# Microcontroller.net
KiCad netlist of a schematic drawn in Altium Designer
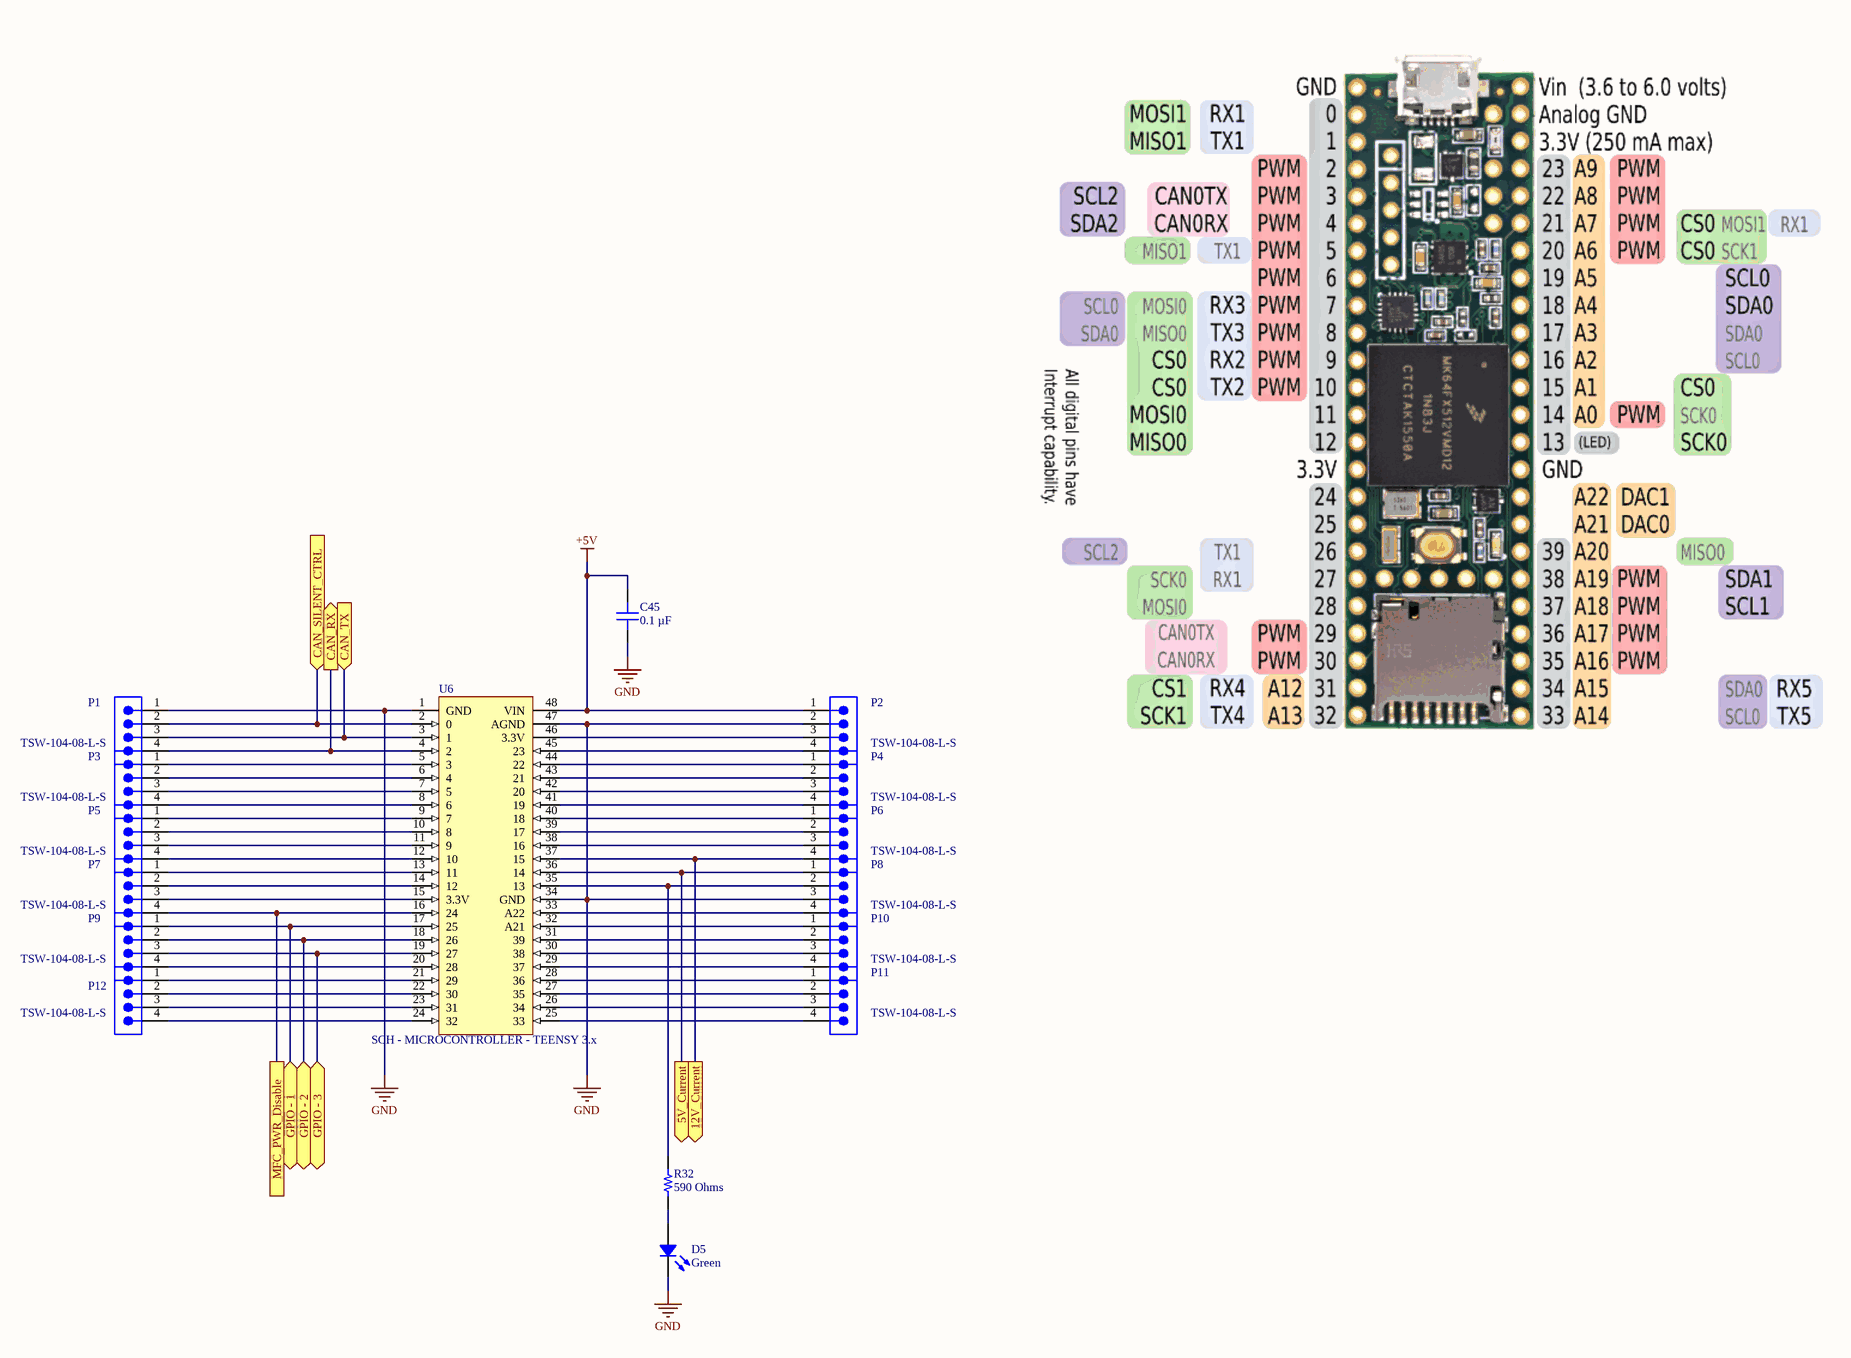
[diagram p0: Microcontroller.SchDoc]

(export (version "E")
  (design (tool "Eeschema 10.0.6"))
  (components
    (comp (ref "C45")
      (value "0.1 µF")
      (footprint "CAP 0603_1608")
      (description "CAP CER 0.1UF 50V X7R 0603")
      (fields
        (field (name "PART NUMBER") "CL10B104KB8NNWC")
        (field (name "MANUFACTURER") "Samsung Electro-Mechanics")
      )
      (libsource (lib "Celestial Altium Library - altium_library") (part "Capacitor"))
    )
    (comp (ref "D5")
      (value "Green")
      (footprint "LED 0603_1608 GREEN")
      (description "LED GREEN CLEAR CHIP SMD")
      (fields (field (name "PART NUMBER") "LTST-C193KGKT-5A") (field (name "MANUFACTURER") "Lite-On Inc."))
      (libsource (lib "Celestial Altium Library - altium_library") (part "LED"))
    )
    (comp (ref "P1")
      (value "TSW-104-08-L-S")
      (footprint "SMTC-TSW-104-08-X-S")
      (description "0.025\" SQ Post Header, Through-hole, Vertical, -55 to 125 degC, 2.54 mm Pitch, 4-Pin, Male, RoHS")
      (fields (field (name "MANUFACTURER") "Samtec"))
      (libsource (lib "Altium Content Vault") (part "SMTC-TSW-104-08-X-S"))
    )
    (comp (ref "P2")
      (value "TSW-104-08-L-S")
      (footprint "SMTC-TSW-104-08-X-S")
      (description "0.025\" SQ Post Header, Through-hole, Vertical, -55 to 125 degC, 2.54 mm Pitch, 4-Pin, Male, RoHS")
      (fields (field (name "MANUFACTURER") "Samtec"))
      (libsource (lib "Altium Content Vault") (part "SMTC-TSW-104-08-X-S"))
    )
    (comp (ref "P3")
      (value "TSW-104-08-L-S")
      (footprint "SMTC-TSW-104-08-X-S")
      (description "0.025\" SQ Post Header, Through-hole, Vertical, -55 to 125 degC, 2.54 mm Pitch, 4-Pin, Male, RoHS")
      (fields (field (name "MANUFACTURER") "Samtec"))
      (libsource (lib "Altium Content Vault") (part "SMTC-TSW-104-08-X-S"))
    )
    (comp (ref "P4")
      (value "TSW-104-08-L-S")
      (footprint "SMTC-TSW-104-08-X-S")
      (description "0.025\" SQ Post Header, Through-hole, Vertical, -55 to 125 degC, 2.54 mm Pitch, 4-Pin, Male, RoHS")
      (fields (field (name "MANUFACTURER") "Samtec"))
      (libsource (lib "Altium Content Vault") (part "SMTC-TSW-104-08-X-S"))
    )
    (comp (ref "P5")
      (value "TSW-104-08-L-S")
      (footprint "SMTC-TSW-104-08-X-S")
      (description "0.025\" SQ Post Header, Through-hole, Vertical, -55 to 125 degC, 2.54 mm Pitch, 4-Pin, Male, RoHS")
      (fields (field (name "MANUFACTURER") "Samtec"))
      (libsource (lib "Altium Content Vault") (part "SMTC-TSW-104-08-X-S"))
    )
    (comp (ref "P6")
      (value "TSW-104-08-L-S")
      (footprint "SMTC-TSW-104-08-X-S")
      (description "0.025\" SQ Post Header, Through-hole, Vertical, -55 to 125 degC, 2.54 mm Pitch, 4-Pin, Male, RoHS")
      (fields (field (name "MANUFACTURER") "Samtec"))
      (libsource (lib "Altium Content Vault") (part "SMTC-TSW-104-08-X-S"))
    )
    (comp (ref "P7")
      (value "TSW-104-08-L-S")
      (footprint "SMTC-TSW-104-08-X-S")
      (description "0.025\" SQ Post Header, Through-hole, Vertical, -55 to 125 degC, 2.54 mm Pitch, 4-Pin, Male, RoHS")
      (fields (field (name "MANUFACTURER") "Samtec"))
      (libsource (lib "Altium Content Vault") (part "SMTC-TSW-104-08-X-S"))
    )
    (comp (ref "P8")
      (value "TSW-104-08-L-S")
      (footprint "SMTC-TSW-104-08-X-S")
      (description "0.025\" SQ Post Header, Through-hole, Vertical, -55 to 125 degC, 2.54 mm Pitch, 4-Pin, Male, RoHS")
      (fields (field (name "MANUFACTURER") "Samtec"))
      (libsource (lib "Altium Content Vault") (part "SMTC-TSW-104-08-X-S"))
    )
    (comp (ref "P9")
      (value "TSW-104-08-L-S")
      (footprint "SMTC-TSW-104-08-X-S")
      (description "0.025\" SQ Post Header, Through-hole, Vertical, -55 to 125 degC, 2.54 mm Pitch, 4-Pin, Male, RoHS")
      (fields (field (name "MANUFACTURER") "Samtec"))
      (libsource (lib "Altium Content Vault") (part "SMTC-TSW-104-08-X-S"))
    )
    (comp (ref "P10")
      (value "TSW-104-08-L-S")
      (footprint "SMTC-TSW-104-08-X-S")
      (description "0.025\" SQ Post Header, Through-hole, Vertical, -55 to 125 degC, 2.54 mm Pitch, 4-Pin, Male, RoHS")
      (fields (field (name "MANUFACTURER") "Samtec"))
      (libsource (lib "Altium Content Vault") (part "SMTC-TSW-104-08-X-S"))
    )
    (comp (ref "P11")
      (value "TSW-104-08-L-S")
      (footprint "SMTC-TSW-104-08-X-S")
      (description "0.025\" SQ Post Header, Through-hole, Vertical, -55 to 125 degC, 2.54 mm Pitch, 4-Pin, Male, RoHS")
      (fields (field (name "MANUFACTURER") "Samtec"))
      (libsource (lib "Altium Content Vault") (part "SMTC-TSW-104-08-X-S"))
    )
    (comp (ref "P12")
      (value "TSW-104-08-L-S")
      (footprint "SMTC-TSW-104-08-X-S")
      (description "0.025\" SQ Post Header, Through-hole, Vertical, -55 to 125 degC, 2.54 mm Pitch, 4-Pin, Male, RoHS")
      (fields (field (name "MANUFACTURER") "Samtec"))
      (libsource (lib "Altium Content Vault") (part "SMTC-TSW-104-08-X-S"))
    )
    (comp (ref "R32")
      (value "590 Ohms")
      (footprint "RES 0603_1608")
      (description "RES 590 OHM 1% 1/10W 0603")
      (fields
        (field (name "PART NUMBER") "RMCF0603FT590R")
        (field (name "MANUFACTURER") "Stackpole Electronics Inc")
      )
      (libsource (lib "Celestial Altium Library - altium_library") (part "Resistor"))
    )
    (comp (ref "U6")
      (value "SCH - MICROCONTROLLER - TEENSY 3.x")
      (footprint "PCB - THRU - TEENSY 3.x")
      (libsource (lib "HAB_ICs") (part "SCH - MICROCONTROLLER - TEENSY 3.x"))
    )
  )
  (nets
    (net (code "1") (name "+5V") (class "Default")
      (node (ref "C45") (pin "1") (pinfunction "1_1") (pintype "passive"))
      (node (ref "P2") (pin "1") (pinfunction "1_1") (pintype "passive"))
      (node (ref "U6") (pin "48") (pinfunction "VIN_48") (pintype "power_in"))
    )
    (net (code "2") (name "/5V_Current") (class "Default")
      (node (ref "P8") (pin "1") (pinfunction "1_1") (pintype "passive"))
      (node (ref "U6") (pin "36") (pinfunction "14_36") (pintype "input"))
    )
    (net (code "3") (name "/12V_Current") (class "Default")
      (node (ref "P6") (pin "4") (pinfunction "4_4") (pintype "passive"))
      (node (ref "U6") (pin "37") (pinfunction "15_37") (pintype "input"))
    )
    (net (code "4") (name "/CAN_RX") (class "Default")
      (node (ref "P1") (pin "4") (pinfunction "4_4") (pintype "passive"))
      (node (ref "U6") (pin "4") (pinfunction "2_4") (pintype "input"))
    )
    (net (code "5") (name "/CAN_SILENT_CTRL") (class "Default")
      (node (ref "P1") (pin "2") (pinfunction "2_2") (pintype "passive"))
      (node (ref "U6") (pin "2") (pinfunction "0_2") (pintype "input"))
    )
    (net (code "6") (name "/CAN_TX") (class "Default")
      (node (ref "P1") (pin "3") (pinfunction "3_3") (pintype "passive"))
      (node (ref "U6") (pin "3") (pinfunction "1_3") (pintype "input"))
    )
    (net (code "7") (name "/GPIO - 1") (class "Default")
      (node (ref "P9") (pin "1") (pinfunction "1_1") (pintype "passive"))
      (node (ref "U6") (pin "17") (pinfunction "25_17") (pintype "input"))
    )
    (net (code "8") (name "/GPIO - 2") (class "Default")
      (node (ref "P9") (pin "2") (pinfunction "2_2") (pintype "passive"))
      (node (ref "U6") (pin "18") (pinfunction "26_18") (pintype "input"))
    )
    (net (code "9") (name "/GPIO - 3") (class "Default")
      (node (ref "P9") (pin "3") (pinfunction "3_3") (pintype "passive"))
      (node (ref "U6") (pin "19") (pinfunction "27_19") (pintype "input"))
    )
    (net (code "10") (name "/MFC_PWR_Disable") (class "Default")
      (node (ref "P7") (pin "4") (pinfunction "4_4") (pintype "passive"))
      (node (ref "U6") (pin "16") (pinfunction "24_16") (pintype "input"))
    )
    (net (code "11") (name "GND") (class "Default")
      (node (ref "C45") (pin "2") (pinfunction "2_2") (pintype "passive"))
      (node (ref "D5") (pin "2") (pinfunction "2_2") (pintype "passive"))
      (node (ref "P1") (pin "1") (pinfunction "1_1") (pintype "passive"))
      (node (ref "P2") (pin "2") (pinfunction "2_2") (pintype "passive"))
      (node (ref "P8") (pin "3") (pinfunction "3_3") (pintype "passive"))
      (node (ref "U6") (pin "1") (pinfunction "GND_1") (pintype "power_in"))
      (node (ref "U6") (pin "34") (pinfunction "GND_34") (pintype "input"))
      (node (ref "U6") (pin "47") (pinfunction "AGND_47") (pintype "power_in"))
    )
    (net (code "12") (name "Net-(D5-Pad1)") (class "Default")
      (node (ref "D5") (pin "1") (pinfunction "1_1") (pintype "passive"))
      (node (ref "R32") (pin "1") (pinfunction "1_1") (pintype "passive"))
    )
    (net (code "13") (name "Net-(P2-Pad3)") (class "Default")
      (node (ref "P2") (pin "3") (pinfunction "3_3") (pintype "passive"))
      (node (ref "U6") (pin "46") (pinfunction "3.3V_46") (pintype "power_in"))
    )
    (net (code "14") (name "Net-(P7-Pad3)") (class "Default")
      (node (ref "P7") (pin "3") (pinfunction "3_3") (pintype "passive"))
      (node (ref "U6") (pin "15") (pinfunction "3.3V_15") (pintype "input"))
    )
    (net (code "15") (name "Net-(U6-3)") (class "Default")
      (node (ref "P3") (pin "1") (pinfunction "1_1") (pintype "passive"))
      (node (ref "U6") (pin "5") (pinfunction "3_5") (pintype "input"))
    )
    (net (code "16") (name "Net-(U6-4)") (class "Default")
      (node (ref "P3") (pin "2") (pinfunction "2_2") (pintype "passive"))
      (node (ref "U6") (pin "6") (pinfunction "4_6") (pintype "input"))
    )
    (net (code "17") (name "Net-(U6-5)") (class "Default")
      (node (ref "P3") (pin "3") (pinfunction "3_3") (pintype "passive"))
      (node (ref "U6") (pin "7") (pinfunction "5_7") (pintype "input"))
    )
    (net (code "18") (name "Net-(U6-6)") (class "Default")
      (node (ref "P3") (pin "4") (pinfunction "4_4") (pintype "passive"))
      (node (ref "U6") (pin "8") (pinfunction "6_8") (pintype "input"))
    )
    (net (code "19") (name "Net-(U6-7)") (class "Default")
      (node (ref "P5") (pin "1") (pinfunction "1_1") (pintype "passive"))
      (node (ref "U6") (pin "9") (pinfunction "7_9") (pintype "input"))
    )
    (net (code "20") (name "Net-(U6-8)") (class "Default")
      (node (ref "P5") (pin "2") (pinfunction "2_2") (pintype "passive"))
      (node (ref "U6") (pin "10") (pinfunction "8_10") (pintype "input"))
    )
    (net (code "21") (name "Net-(U6-9)") (class "Default")
      (node (ref "P5") (pin "3") (pinfunction "3_3") (pintype "passive"))
      (node (ref "U6") (pin "11") (pinfunction "9_11") (pintype "input"))
    )
    (net (code "22") (name "Net-(U6-10)") (class "Default")
      (node (ref "P5") (pin "4") (pinfunction "4_4") (pintype "passive"))
      (node (ref "U6") (pin "12") (pinfunction "10_12") (pintype "input"))
    )
    (net (code "23") (name "Net-(U6-11)") (class "Default")
      (node (ref "P7") (pin "1") (pinfunction "1_1") (pintype "passive"))
      (node (ref "U6") (pin "13") (pinfunction "11_13") (pintype "input"))
    )
    (net (code "24") (name "Net-(U6-12)") (class "Default")
      (node (ref "P7") (pin "2") (pinfunction "2_2") (pintype "passive"))
      (node (ref "U6") (pin "14") (pinfunction "12_14") (pintype "input"))
    )
    (net (code "25") (name "Net-(U6-13)") (class "Default")
      (node (ref "P8") (pin "2") (pinfunction "2_2") (pintype "passive"))
      (node (ref "R32") (pin "2") (pinfunction "2_2") (pintype "passive"))
      (node (ref "U6") (pin "35") (pinfunction "13_35") (pintype "input"))
    )
    (net (code "26") (name "Net-(U6-16)") (class "Default")
      (node (ref "P6") (pin "3") (pinfunction "3_3") (pintype "passive"))
      (node (ref "U6") (pin "38") (pinfunction "16_38") (pintype "input"))
    )
    (net (code "27") (name "Net-(U6-17)") (class "Default")
      (node (ref "P6") (pin "2") (pinfunction "2_2") (pintype "passive"))
      (node (ref "U6") (pin "39") (pinfunction "17_39") (pintype "input"))
    )
    (net (code "28") (name "Net-(U6-18)") (class "Default")
      (node (ref "P6") (pin "1") (pinfunction "1_1") (pintype "passive"))
      (node (ref "U6") (pin "40") (pinfunction "18_40") (pintype "input"))
    )
    (net (code "29") (name "Net-(U6-19)") (class "Default")
      (node (ref "P4") (pin "4") (pinfunction "4_4") (pintype "passive"))
      (node (ref "U6") (pin "41") (pinfunction "19_41") (pintype "input"))
    )
    (net (code "30") (name "Net-(U6-20)") (class "Default")
      (node (ref "P4") (pin "3") (pinfunction "3_3") (pintype "passive"))
      (node (ref "U6") (pin "42") (pinfunction "20_42") (pintype "input"))
    )
    (net (code "31") (name "Net-(U6-21)") (class "Default")
      (node (ref "P4") (pin "2") (pinfunction "2_2") (pintype "passive"))
      (node (ref "U6") (pin "43") (pinfunction "21_43") (pintype "input"))
    )
    (net (code "32") (name "Net-(U6-22)") (class "Default")
      (node (ref "P4") (pin "1") (pinfunction "1_1") (pintype "passive"))
      (node (ref "U6") (pin "44") (pinfunction "22_44") (pintype "input"))
    )
    (net (code "33") (name "Net-(U6-23)") (class "Default")
      (node (ref "P2") (pin "4") (pinfunction "4_4") (pintype "passive"))
      (node (ref "U6") (pin "45") (pinfunction "23_45") (pintype "input"))
    )
    (net (code "34") (name "Net-(U6-28)") (class "Default")
      (node (ref "P9") (pin "4") (pinfunction "4_4") (pintype "passive"))
      (node (ref "U6") (pin "20") (pinfunction "28_20") (pintype "input"))
    )
    (net (code "35") (name "Net-(U6-29)") (class "Default")
      (node (ref "P12") (pin "1") (pinfunction "1_1") (pintype "passive"))
      (node (ref "U6") (pin "21") (pinfunction "29_21") (pintype "input"))
    )
    (net (code "36") (name "Net-(U6-30)") (class "Default")
      (node (ref "P12") (pin "2") (pinfunction "2_2") (pintype "passive"))
      (node (ref "U6") (pin "22") (pinfunction "30_22") (pintype "input"))
    )
    (net (code "37") (name "Net-(U6-31)") (class "Default")
      (node (ref "P12") (pin "3") (pinfunction "3_3") (pintype "passive"))
      (node (ref "U6") (pin "23") (pinfunction "31_23") (pintype "input"))
    )
    (net (code "38") (name "Net-(U6-32)") (class "Default")
      (node (ref "P12") (pin "4") (pinfunction "4_4") (pintype "passive"))
      (node (ref "U6") (pin "24") (pinfunction "32_24") (pintype "input"))
    )
    (net (code "39") (name "Net-(U6-33)") (class "Default")
      (node (ref "P11") (pin "4") (pinfunction "4_4") (pintype "passive"))
      (node (ref "U6") (pin "25") (pinfunction "33_25") (pintype "input"))
    )
    (net (code "40") (name "Net-(U6-34)") (class "Default")
      (node (ref "P11") (pin "3") (pinfunction "3_3") (pintype "passive"))
      (node (ref "U6") (pin "26") (pinfunction "34_26") (pintype "input"))
    )
    (net (code "41") (name "Net-(U6-35)") (class "Default")
      (node (ref "P11") (pin "2") (pinfunction "2_2") (pintype "passive"))
      (node (ref "U6") (pin "27") (pinfunction "35_27") (pintype "input"))
    )
    (net (code "42") (name "Net-(U6-36)") (class "Default")
      (node (ref "P11") (pin "1") (pinfunction "1_1") (pintype "passive"))
      (node (ref "U6") (pin "28") (pinfunction "36_28") (pintype "input"))
    )
    (net (code "43") (name "Net-(U6-37)") (class "Default")
      (node (ref "P10") (pin "4") (pinfunction "4_4") (pintype "passive"))
      (node (ref "U6") (pin "29") (pinfunction "37_29") (pintype "input"))
    )
    (net (code "44") (name "Net-(U6-38)") (class "Default")
      (node (ref "P10") (pin "3") (pinfunction "3_3") (pintype "passive"))
      (node (ref "U6") (pin "30") (pinfunction "38_30") (pintype "input"))
    )
    (net (code "45") (name "Net-(U6-39)") (class "Default")
      (node (ref "P10") (pin "2") (pinfunction "2_2") (pintype "passive"))
      (node (ref "U6") (pin "31") (pinfunction "39_31") (pintype "input"))
    )
    (net (code "46") (name "Net-(U6-A21)") (class "Default")
      (node (ref "P10") (pin "1") (pinfunction "1_1") (pintype "passive"))
      (node (ref "U6") (pin "32") (pinfunction "A21_32") (pintype "input"))
    )
    (net (code "47") (name "Net-(U6-A22)") (class "Default")
      (node (ref "P8") (pin "4") (pinfunction "4_4") (pintype "passive"))
      (node (ref "U6") (pin "33") (pinfunction "A22_33") (pintype "input"))
    )
  )
)
